# Top_sheet.net
KiCad netlist of a schematic drawn in Altium Designer
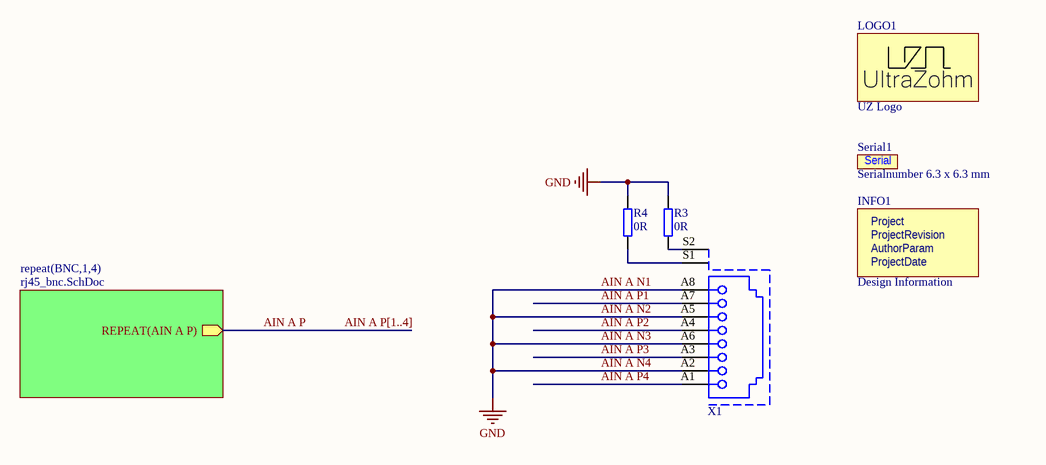
[diagram p0: Top_sheet.SchDoc]

(export (version "E")
  (design (tool "Eeschema 10.0.6"))
  (components
    (comp (ref "INFO1")
      (value "Design Information")
      (footprint "Design_info")
      (fields (field (name "MANUFACTURER") "UltraZohm") (field (name "CREATED FROM") "MGremer"))
      (libsource (lib "user") (part "Design_info"))
    )
    (comp (ref "LOGO1")
      (value "UZ Logo")
      (footprint "UZ_Logo_small")
      (fields
        (field (name "MANUFACTURER PART NUMBER") "Logo small")
        (field (name "MANUFACTURER") "UltraZohm")
        (field (name "CREATED") "Jan2021_Liegmann")
        (field (name "CREATED FROM") "MGremer")
      )
      (libsource (lib "user") (part "UZ Logo"))
    )
    (comp (ref "R3")
      (value "0R")
      (footprint "R_0603_TE")
      (description "Generic resistor")
      (fields
        (field (name "MANUFACTURER PART NUMBER") "UZgen_R_0603_0R")
        (field (name "MANUFACTURER") "UZgen")
        (field (name "CREATED FROM") "UZgenTool")
      )
      (libsource (lib "user") (part "RES"))
    )
    (comp (ref "R4")
      (value "0R")
      (footprint "R_0603_TE")
      (description "Generic resistor")
      (fields
        (field (name "MANUFACTURER PART NUMBER") "UZgen_R_0603_0R")
        (field (name "MANUFACTURER") "UZgen")
        (field (name "CREATED FROM") "UZgenTool")
      )
      (libsource (lib "user") (part "RES"))
    )
    (comp (ref "Serial1")
      (value "Serialnumber 6.3 x 6.3 mm")
      (footprint "SERIAL_6.3X6.3MM")
      (description "Serial Number")
      (fields
        (field (name "MANUFACTURER") "UltraZohm")
        (field (name "CREATED") "2018_09_18_AGeiger")
        (field (name "CREATED FROM") "MGremer")
      )
      (libsource (lib "user") (part "SerialNumber"))
    )
    (comp (ref "X1")
      (value "~")
      (footprint "R-RJ45R10P-B000")
      (fields
        (field (name "MANUFACTURER PART NUMBER") "R-RJ45R10P-B000")
        (field (name "MANUFACTURER") "Ckmtw(Shenzhen Cankemeng)")
        (field (name "LCSC PART NUMBER") "C386758")
        (field (name "CREATED FROM") "KIlhan")
      )
      (libsource (lib "user") (part "R-RJ45R10P-B000"))
    )
  )
  (nets
    (net (code "2") (name "/AIN A P1") (class "Default")
      (node (ref "X1") (pin "A7") (pinfunction "A7_A7") (pintype "passive"))
    )
    (net (code "3") (name "/AIN A P2") (class "Default")
      (node (ref "X1") (pin "A4") (pinfunction "A4_A4") (pintype "passive"))
    )
    (net (code "4") (name "/AIN A P3") (class "Default")
      (node (ref "X1") (pin "A3") (pinfunction "A3_A3") (pintype "passive"))
    )
    (net (code "5") (name "/AIN A P4") (class "Default")
      (node (ref "X1") (pin "A1") (pinfunction "A1_A1") (pintype "passive"))
    )
    (net (code "7") (name "GND") (class "Default")
      (node (ref "R3") (pin "1") (pinfunction "1_1") (pintype "passive"))
      (node (ref "R4") (pin "1") (pinfunction "1_1") (pintype "passive"))
      (node (ref "X1") (pin "A2") (pinfunction "A2_A2") (pintype "passive"))
      (node (ref "X1") (pin "A5") (pinfunction "A5_A5") (pintype "passive"))
      (node (ref "X1") (pin "A6") (pinfunction "A6_A6") (pintype "passive"))
      (node (ref "X1") (pin "A8") (pinfunction "A8_A8") (pintype "passive"))
    )
    (net (code "8") (name "Net-(R3-Pad2)") (class "Default")
      (node (ref "R3") (pin "2") (pinfunction "2_2") (pintype "passive"))
      (node (ref "X1") (pin "S2") (pinfunction "S2_S2") (pintype "passive"))
    )
    (net (code "9") (name "Net-(R4-Pad2)") (class "Default")
      (node (ref "R4") (pin "2") (pinfunction "2_2") (pintype "passive"))
      (node (ref "X1") (pin "S1") (pinfunction "S1_S1") (pintype "passive"))
    )
  )
)
